# TDSensorSchematic.net
KiCad netlist of a schematic drawn in EAGLE
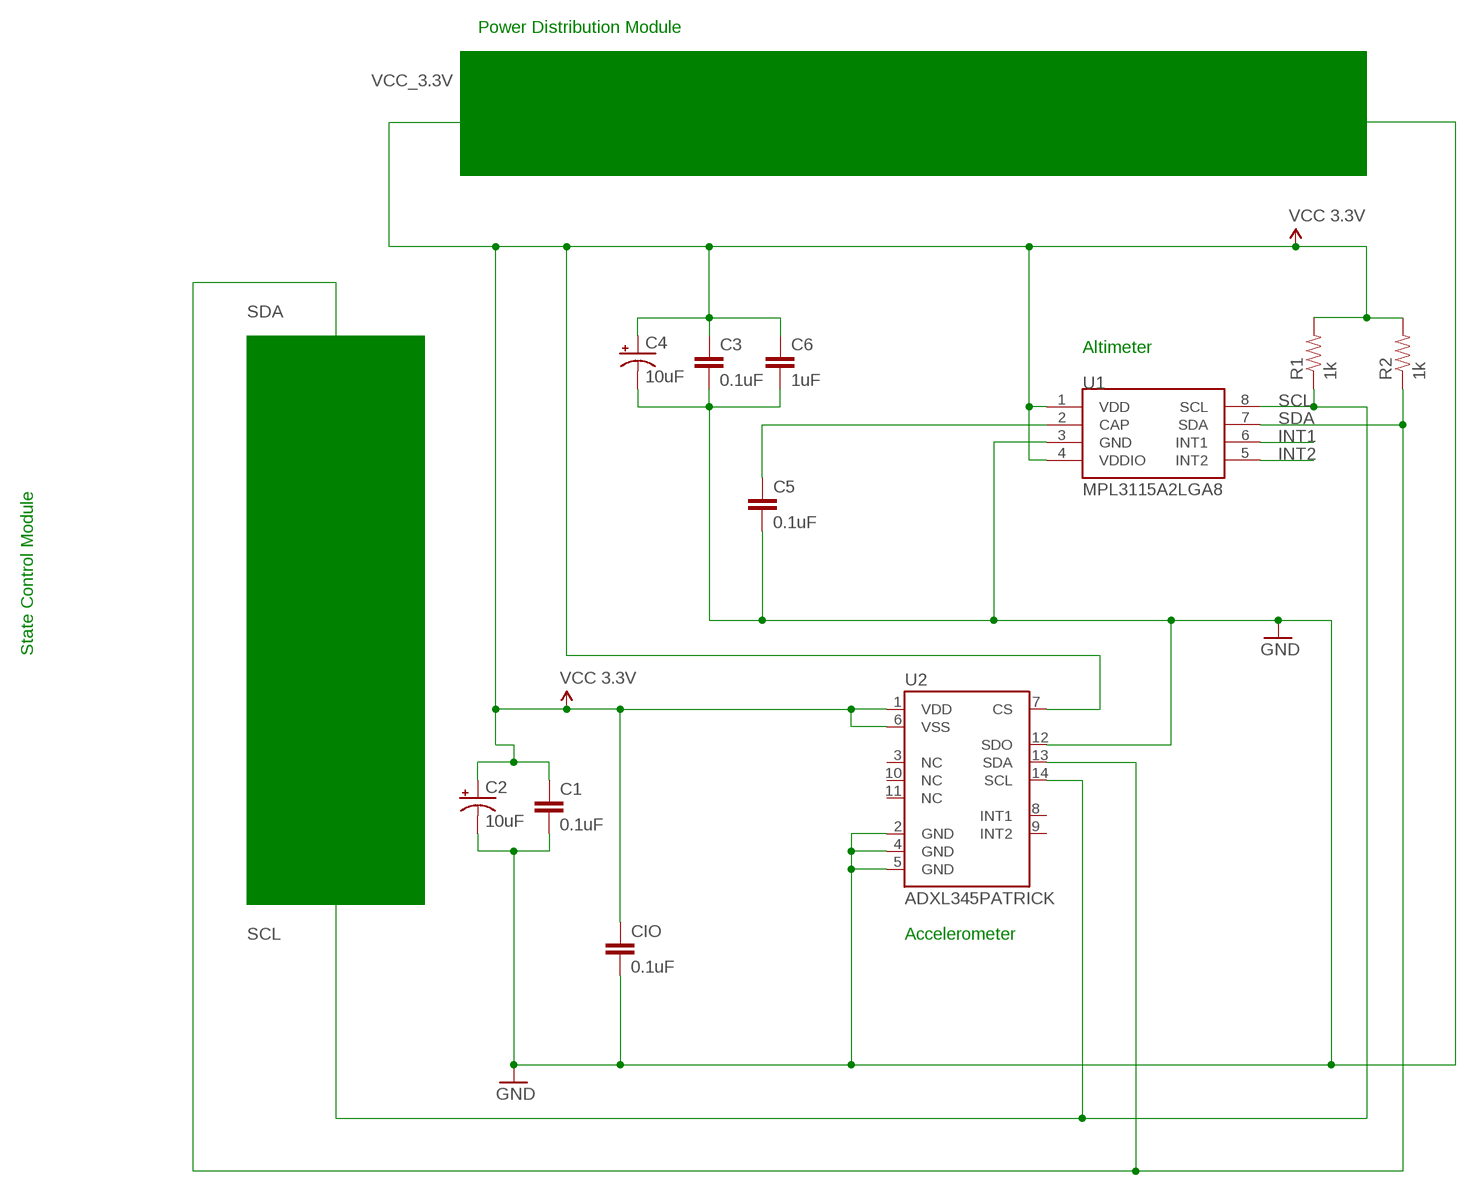
[diagram p0: schematic, sheet 1]

(export (version "E")
  (design (tool "Eeschema 10.0.6"))
  (components
    (comp (ref "C1")
      (value "0.1uF")
      (footprint "eagle-import:0603-CAP")
      (libsource (lib "eagle-import") (part "CAP0603-CAP"))
    )
    (comp (ref "C2")
      (value "10uF")
      (footprint "eagle-import:EIA3216")
      (libsource (lib "eagle-import") (part "CAP_POL1206"))
    )
    (comp (ref "C3")
      (value "0.1uF")
      (footprint "eagle-import:0402-CAP")
      (libsource (lib "eagle-import") (part "CAP0402-CAP"))
    )
    (comp (ref "C4")
      (value "10uF")
      (footprint "eagle-import:EIA3216")
      (libsource (lib "eagle-import") (part "CAP_POL1206"))
    )
    (comp (ref "C5")
      (value "0.1uF")
      (footprint "eagle-import:0402-CAP")
      (libsource (lib "eagle-import") (part "CAP0402-CAP"))
    )
    (comp (ref "C6")
      (value "1uF")
      (footprint "eagle-import:0402-CAP")
      (libsource (lib "eagle-import") (part "CAP0402-CAP"))
    )
    (comp (ref "CIO")
      (value "0.1uF")
      (footprint "eagle-import:0603-CAP")
      (libsource (lib "eagle-import") (part "CAP0603-CAP"))
    )
    (comp (ref "R1")
      (value "1k")
      (footprint "eagle-import:0402-RES")
      (libsource (lib "eagle-import") (part "RESISTOR0402-RES"))
    )
    (comp (ref "R2")
      (value "1k")
      (footprint "eagle-import:0402-RES")
      (libsource (lib "eagle-import") (part "RESISTOR0402-RES"))
    )
    (comp (ref "U1")
      (value "MPL3115A2LGA8")
      (footprint "eagle-import:LGA8")
      (libsource (lib "eagle-import") (part "MPL3115A2LGA8"))
    )
    (comp (ref "U2")
      (value "ADXL345PATRICK")
      (footprint "eagle-import:LGA14_1_1_PATRICK")
      (libsource (lib "eagle-import") (part "ADXL345PATRICK"))
    )
  )
  (nets
    (net (code "1") (name "/INT1") (class "Default")
      (node (ref "U1") (pin "6") (pinfunction "INT1_6") (pintype "bidirectional"))
    )
    (net (code "2") (name "/INT2") (class "Default")
      (node (ref "U1") (pin "5") (pinfunction "INT2_5") (pintype "bidirectional"))
    )
    (net (code "3") (name "/SCL") (class "Default")
      (node (ref "R1") (pin "1") (pinfunction "1_1") (pintype "passive"))
      (node (ref "U1") (pin "8") (pinfunction "SCL_8") (pintype "bidirectional"))
      (node (ref "U2") (pin "14") (pinfunction "SCL_14") (pintype "bidirectional"))
    )
    (net (code "4") (name "/SDA") (class "Default")
      (node (ref "R2") (pin "1") (pinfunction "1_1") (pintype "passive"))
      (node (ref "U1") (pin "7") (pinfunction "SDA_7") (pintype "bidirectional"))
      (node (ref "U2") (pin "13") (pinfunction "SDA_13") (pintype "bidirectional"))
    )
    (net (code "5") (name "GND") (class "Default")
      (node (ref "C1") (pin "2") (pinfunction "2_2") (pintype "passive"))
      (node (ref "C2") (pin "C") (pinfunction "-_C") (pintype "passive"))
      (node (ref "C3") (pin "2") (pinfunction "2_2") (pintype "passive"))
      (node (ref "C4") (pin "C") (pinfunction "-_C") (pintype "passive"))
      (node (ref "C5") (pin "2") (pinfunction "2_2") (pintype "passive"))
      (node (ref "C6") (pin "2") (pinfunction "2_2") (pintype "passive"))
      (node (ref "CIO") (pin "2") (pinfunction "2_2") (pintype "passive"))
      (node (ref "U1") (pin "3") (pinfunction "GND_3") (pintype "bidirectional"))
      (node (ref "U2") (pin "12") (pinfunction "SDO_12") (pintype "bidirectional"))
      (node (ref "U2") (pin "2") (pinfunction "GND_2") (pintype "bidirectional"))
      (node (ref "U2") (pin "4") (pinfunction "GND_4") (pintype "bidirectional"))
      (node (ref "U2") (pin "5") (pinfunction "GND_5") (pintype "bidirectional"))
    )
    (net (code "6") (name "Net-(U1-CAP)") (class "Default")
      (node (ref "C5") (pin "1") (pinfunction "1_1") (pintype "passive"))
      (node (ref "U1") (pin "2") (pinfunction "CAP_2") (pintype "bidirectional"))
    )
    (net (code "7") (name "VCC 3.3V") (class "Default")
      (node (ref "C1") (pin "1") (pinfunction "1_1") (pintype "passive"))
      (node (ref "C2") (pin "A") (pinfunction "+_A") (pintype "passive"))
      (node (ref "C3") (pin "1") (pinfunction "1_1") (pintype "passive"))
      (node (ref "C4") (pin "A") (pinfunction "+_A") (pintype "passive"))
      (node (ref "C6") (pin "1") (pinfunction "1_1") (pintype "passive"))
      (node (ref "CIO") (pin "1") (pinfunction "1_1") (pintype "passive"))
      (node (ref "R1") (pin "2") (pinfunction "2_2") (pintype "passive"))
      (node (ref "R2") (pin "2") (pinfunction "2_2") (pintype "passive"))
      (node (ref "U1") (pin "1") (pinfunction "VDD_1") (pintype "bidirectional"))
      (node (ref "U1") (pin "4") (pinfunction "VDDIO_4") (pintype "bidirectional"))
      (node (ref "U2") (pin "1") (pinfunction "VDD_1") (pintype "bidirectional"))
      (node (ref "U2") (pin "6") (pinfunction "VSS_6") (pintype "bidirectional"))
      (node (ref "U2") (pin "7") (pinfunction "CS_7") (pintype "bidirectional"))
    )
    (net (code "8") (name "unconnected-(U2-INT1-Pad8)") (class "Default")
      (node (ref "U2") (pin "8") (pinfunction "INT1_8") (pintype "bidirectional"))
    )
    (net (code "9") (name "unconnected-(U2-INT2-Pad9)") (class "Default")
      (node (ref "U2") (pin "9") (pinfunction "INT2_9") (pintype "bidirectional"))
    )
    (net (code "10") (name "unconnected-(U2-NC-Pad3)") (class "Default")
      (node (ref "U2") (pin "3") (pinfunction "NC_3") (pintype "bidirectional"))
    )
    (net (code "11") (name "unconnected-(U2-NC-Pad10)") (class "Default")
      (node (ref "U2") (pin "10") (pinfunction "NC_10") (pintype "bidirectional"))
    )
    (net (code "12") (name "unconnected-(U2-NC-Pad11)") (class "Default")
      (node (ref "U2") (pin "11") (pinfunction "NC_11") (pintype "bidirectional"))
    )
  )
)
